# ProPrj_2025_7__2025-07-14.net
KiCad netlist of a schematic drawn in EasyEDA Pro
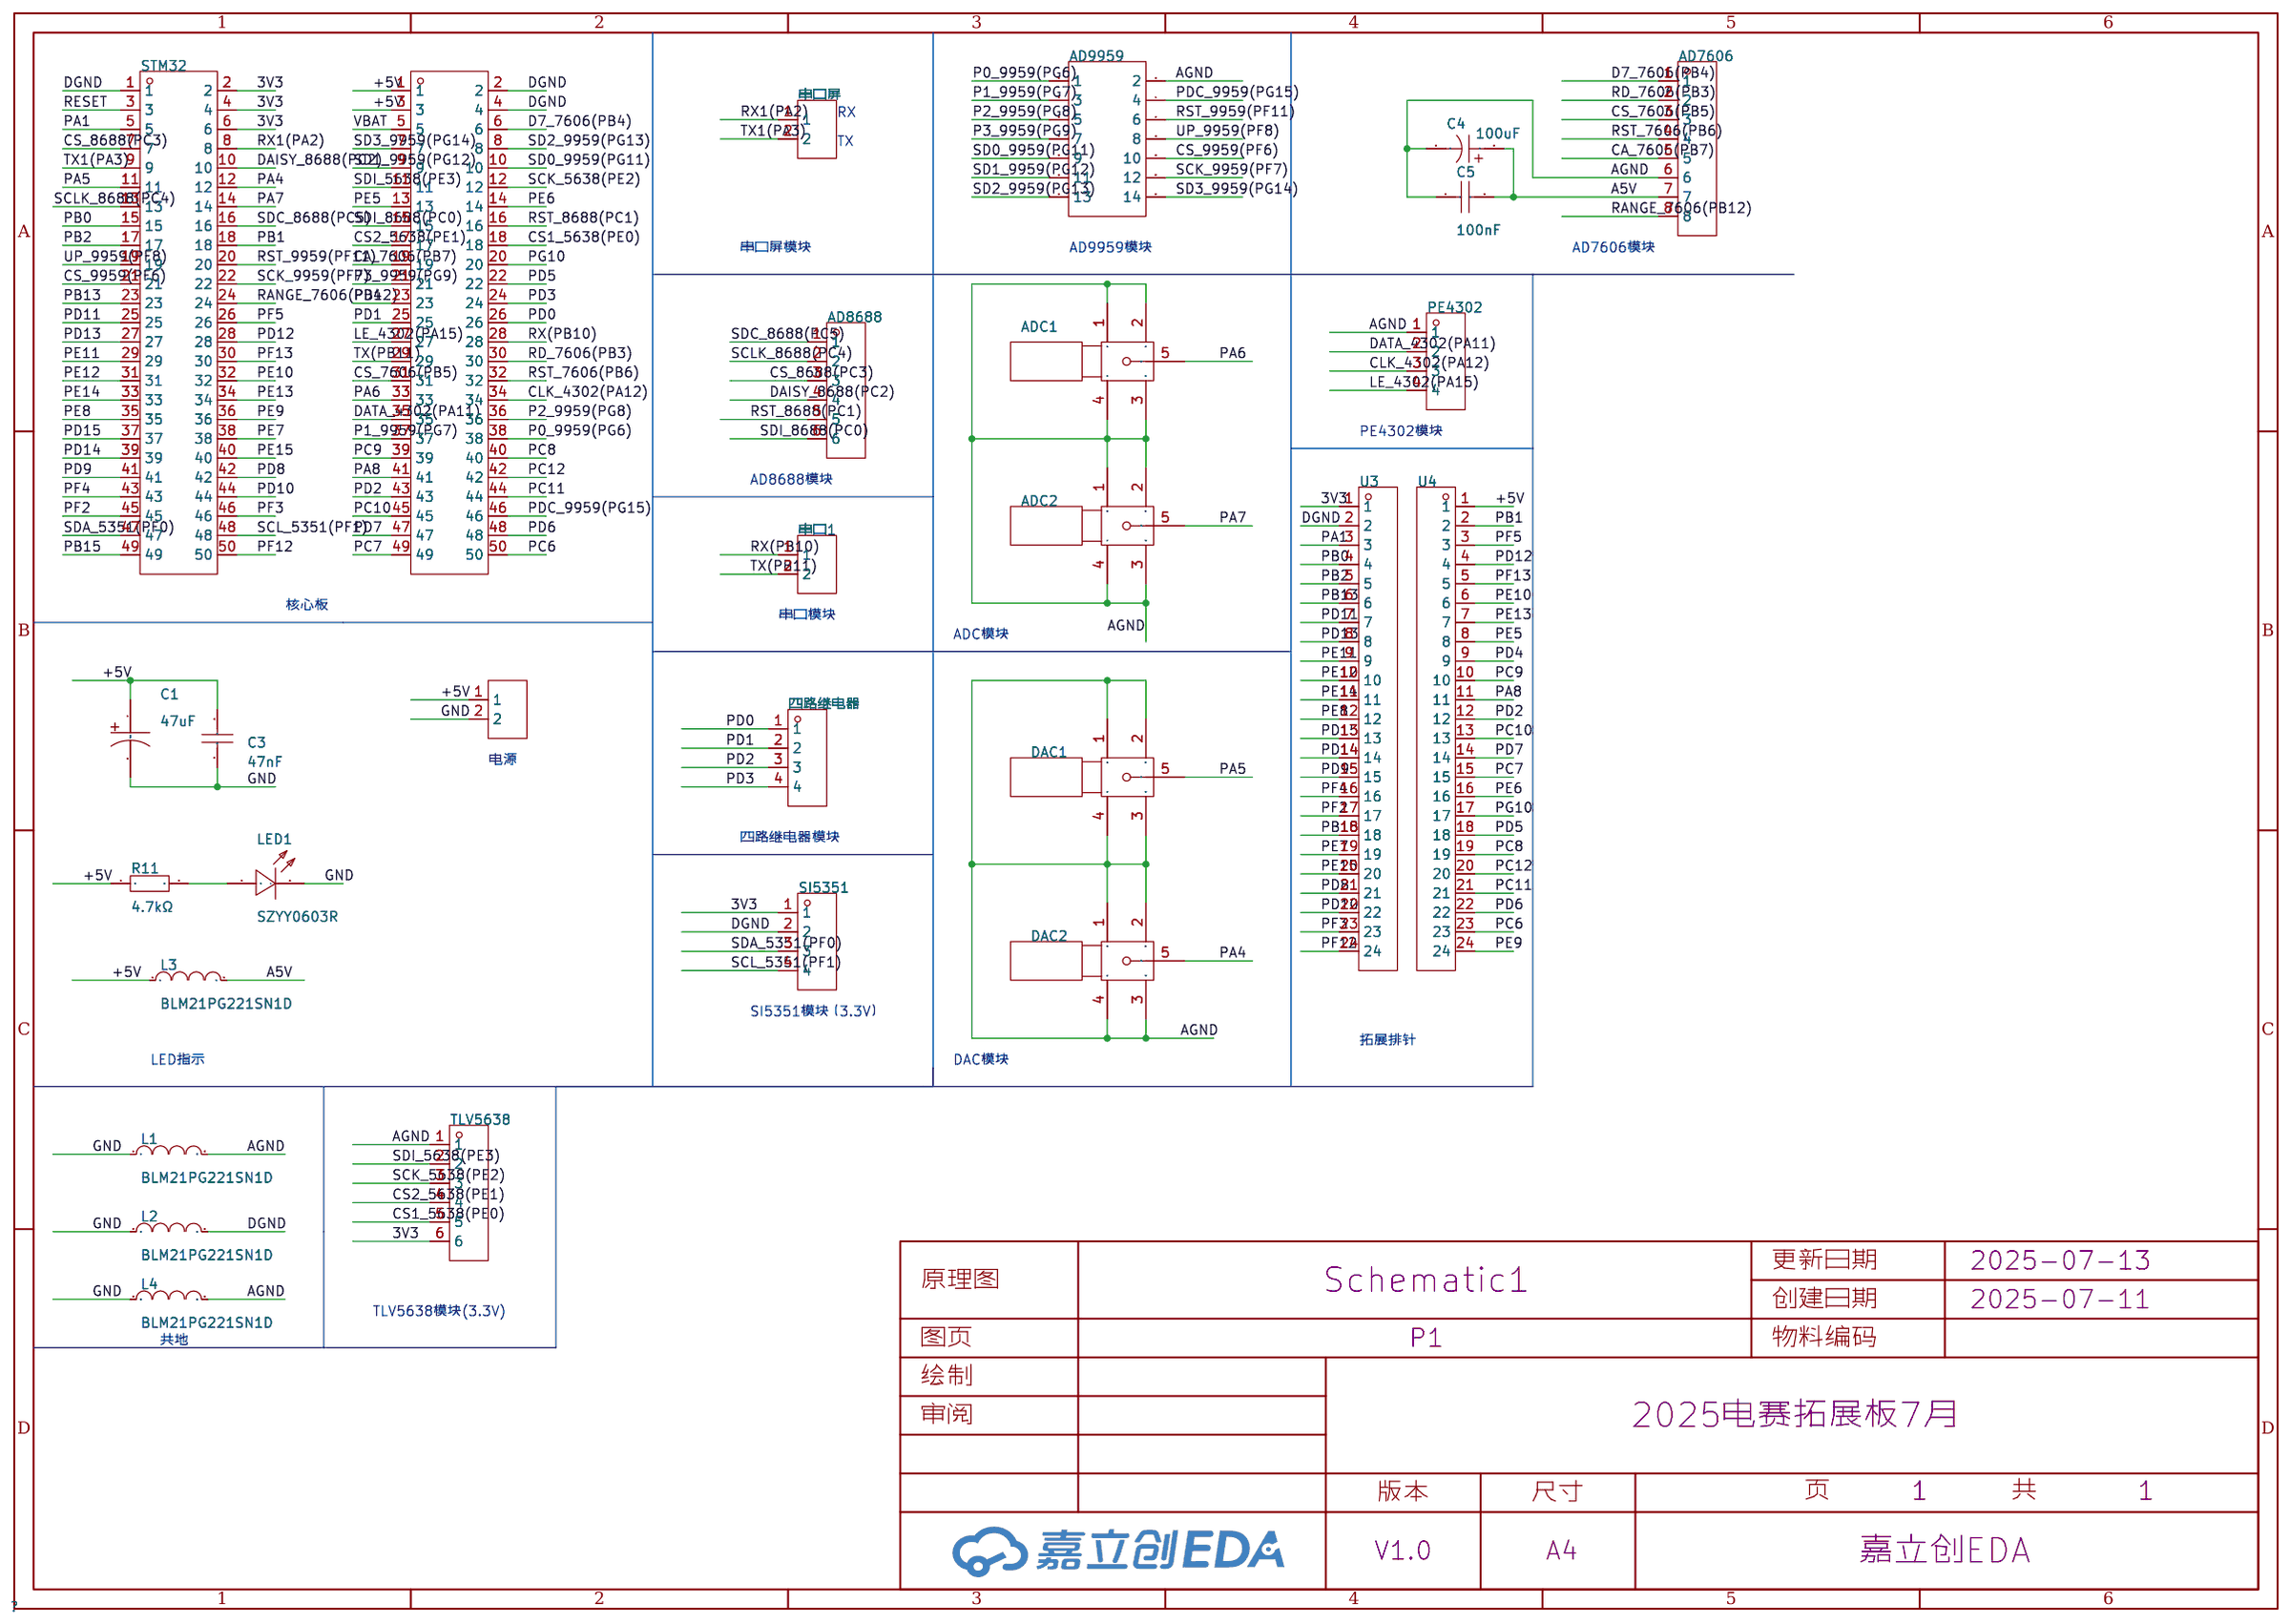
[diagram p0: schematic sheet]

(export (version "E")
  (design (tool "Eeschema 10.0.6"))
  (components
    (comp (ref "AD7606")
      (value "ZX-XH2.54-8PZZ")
      (footprint "easyedapro:CONN-TH_8P-P2.50-XH2.54-8P")
      (fields (field (name "Manufacturer") "Megastar(兆星)"))
      (libsource (lib "easyedapro") (part "ZX-XH2.54-8PZZ"))
    )
    (comp (ref "AD8688")
      (value "ZX-XH2.54-6PZZ")
      (footprint "easyedapro:CONN-TH_6P-P2.50_ZX-XH2.54-6PZZ")
      (fields (field (name "Manufacturer") "Megastar(兆星)"))
      (libsource (lib "easyedapro") (part "ZX-XH2.54-6PZZ"))
    )
    (comp (ref "AD9959")
      (value "2.54-2*7P简牛")
      (footprint "easyedapro:IDC-TH_14P-P2.54-V-R2-C7-S2.54")
      (description "连接器类型:简牛座;间距:2.54mm;结构:2x7P;封装形式:直插;行距:2.54mm;排数:2;每排PIN数:7;触头材质:黄铜;触头镀层:金;")
      (fields (field (name "Manufacturer") "BOOMELE(博穆精密)"))
      (libsource (lib "easyedapro") (part "HDR-IDC-2.54-2X7P"))
    )
    (comp (ref "ADC1")
      (value "BWSMA-KE-P001")
      (footprint "easyedapro:SMA-SMD_BWSMA-KE-P001")
      (description "连接器类型:板端;接口类型:内孔;端口数量:1;接口直径:5.2mm;接口长度/高度:-;频率-最大值:-;射频系列:SMA;阻抗:50Ω;样式:偏脚;工作温度范围:-;")
      (fields (field (name "Manufacturer") "BAT WIRELESS(蝙蝠无线)"))
      (libsource (lib "easyedapro") (part "BWSMA-KE-P001"))
    )
    (comp (ref "ADC2")
      (value "BWSMA-KE-P001")
      (footprint "easyedapro:SMA-SMD_BWSMA-KE-P001")
      (description "连接器类型:板端;接口类型:内孔;端口数量:1;接口直径:5.2mm;接口长度/高度:-;频率-最大值:-;射频系列:SMA;阻抗:50Ω;样式:偏脚;工作温度范围:-;")
      (fields (field (name "Manufacturer") "BAT WIRELESS(蝙蝠无线)"))
      (libsource (lib "easyedapro") (part "BWSMA-KE-P001"))
    )
    (comp (ref "C1")
      (value "47uF")
      (footprint "easyedapro:CAP-TH_BD5.0-P2.00-D0.8-FD")
      (description "容值:47uF;精度:±20%;额定电压:25V;纹波电流:250mA@100kHz;等效串联电阻(ESR):300mΩ@100kHz;")
      (fields
        (field (name "Manufacturer Part") "NXB25V47M5*11 2.5TP")
        (field (name "Manufacturer") "SAMYOUNG(韩国三莹)")
      )
      (libsource (lib "easyedapro") (part "NXB25VB47M5*11_2.5TP"))
    )
    (comp (ref "C3")
      (value "47nF")
      (footprint "easyedapro:C0805")
      (description "容值:47nF;精度:±10%;额定电压:50V;材质(温度系数):X7R;")
      (fields
        (field (name "Manufacturer Part") "CL21B473KBCNNNC")
        (field (name "Manufacturer") "SAMSUNG(三星)")
      )
      (libsource (lib "easyedapro") (part "CL21B473KBCNNNC"))
    )
    (comp (ref "C4")
      (value "100uF")
      (footprint "easyedapro:CAP-TH_BD8.0-P3.50-D0.5-FD")
      (description "容值:100uF;精度:±20%;额定电压:50V;纹波电流:680mA@120Hz;等效串联电阻(ESR):120mΩ;")
      (fields (field (name "Manufacturer Part") "ERG50V100M8X12") (field (name "Manufacturer") "捷而瑞"))
      (libsource (lib "easyedapro") (part "ERG50V100M8X12"))
    )
    (comp (ref "C5")
      (value "100nF")
      (footprint "easyedapro:C0805")
      (description "容值:100nF;精度:±10%;额定电压:50V;材质(温度系数):X7R;")
      (fields
        (field (name "Manufacturer Part") "CL21B104KBCNNNC")
        (field (name "Manufacturer") "SAMSUNG(三星)")
      )
      (libsource (lib "easyedapro") (part "CL21B104KBCNNNC"))
    )
    (comp (ref "DAC1")
      (value "BWSMA-KE-P001")
      (footprint "easyedapro:SMA-SMD_BWSMA-KE-P001")
      (description "连接器类型:板端;接口类型:内孔;端口数量:1;接口直径:5.2mm;接口长度/高度:-;频率-最大值:-;射频系列:SMA;阻抗:50Ω;样式:偏脚;工作温度范围:-;")
      (fields (field (name "Manufacturer") "BAT WIRELESS(蝙蝠无线)"))
      (libsource (lib "easyedapro") (part "BWSMA-KE-P001"))
    )
    (comp (ref "DAC2")
      (value "BWSMA-KE-P001")
      (footprint "easyedapro:SMA-SMD_BWSMA-KE-P001")
      (description "连接器类型:板端;接口类型:内孔;端口数量:1;接口直径:5.2mm;接口长度/高度:-;频率-最大值:-;射频系列:SMA;阻抗:50Ω;样式:偏脚;工作温度范围:-;")
      (fields (field (name "Manufacturer") "BAT WIRELESS(蝙蝠无线)"))
      (libsource (lib "easyedapro") (part "BWSMA-KE-P001"))
    )
    (comp (ref "L1")
      (value "BLM21PG221SN1D")
      (footprint "easyedapro:L0805")
      (description "标称阻抗@测试频率:220Ω@100MHz;误差:±25%;直流电阻(RDC):45mΩ;")
      (fields (field (name "Manufacturer") "muRata(村田)"))
      (libsource (lib "easyedapro") (part "BLM21PG221SN1D"))
    )
    (comp (ref "L2")
      (value "BLM21PG221SN1D")
      (footprint "easyedapro:L0805")
      (description "标称阻抗@测试频率:220Ω@100MHz;误差:±25%;直流电阻(RDC):45mΩ;")
      (fields (field (name "Manufacturer") "muRata(村田)"))
      (libsource (lib "easyedapro") (part "BLM21PG221SN1D"))
    )
    (comp (ref "L3")
      (value "BLM21PG221SN1D")
      (footprint "easyedapro:L0805")
      (description "标称阻抗@测试频率:220Ω@100MHz;误差:±25%;直流电阻(RDC):45mΩ;")
      (fields (field (name "Manufacturer") "muRata(村田)"))
      (libsource (lib "easyedapro") (part "BLM21PG221SN1D"))
    )
    (comp (ref "L4")
      (value "BLM21PG221SN1D")
      (footprint "easyedapro:L0805")
      (description "标称阻抗@测试频率:220Ω@100MHz;误差:±25%;直流电阻(RDC):45mΩ;")
      (fields (field (name "Manufacturer") "muRata(村田)"))
      (libsource (lib "easyedapro") (part "BLM21PG221SN1D"))
    )
    (comp (ref "LED1")
      (value "SZYY0603R")
      (footprint "easyedapro:LED0603-R-RD")
      (fields (field (name "Manufacturer") "yongyu(永裕光电)"))
      (libsource (lib "easyedapro") (part "SZYY0603R"))
    )
    (comp (ref "PE4302")
      (value "ZX-XH2.54-4PZZ")
      (footprint "easyedapro:CONN-TH_4P-P2.50_4PIN")
      (fields (field (name "Manufacturer") "Megastar(兆星)"))
      (libsource (lib "easyedapro") (part "ZX-XH2.54-4PZZ"))
    )
    (comp (ref "R11")
      (value "4.7kΩ")
      (footprint "easyedapro:R0805")
      (description "电阻类型:厚膜电阻;阻值:4.7kΩ;精度:±1%;功率:125mW;最大工作电压:150V;温度系数:±100ppm/°C;")
      (fields
        (field (name "Manufacturer Part") "0805W8F4701T5E")
        (field (name "Manufacturer") "UNI-ROYAL(厚声)")
      )
      (libsource (lib "easyedapro") (part "0805W8F4701T5E"))
    )
    (comp (ref "SI5351")
      (value "ZX-XH2.54-4PZZ")
      (footprint "easyedapro:CONN-TH_4P-P2.50_4PIN")
      (fields (field (name "Manufacturer") "Megastar(兆星)"))
      (libsource (lib "easyedapro") (part "ZX-XH2.54-4PZZ"))
    )
    (comp (ref "STM32")
      (value "ZX-PM2.54-2-25PY")
      (footprint "easyedapro:HDR-TH_50P-P2.54-V-F-R2-C25-S2.54-1")
      (fields (field (name "Manufacturer") "Megastar(兆星)"))
      (libsource (lib "easyedapro") (part "ZX-PM2.54-2-25PY"))
    )
    (comp (ref "TLV5638")
      (value "ZX-XH2.54-6PZZ")
      (footprint "easyedapro:CONN-TH_6P-P2.50_ZX-XH2.54-6PZZ")
      (fields (field (name "Manufacturer") "Megastar(兆星)"))
      (libsource (lib "easyedapro") (part "ZX-XH2.54-6PZZ"))
    )
    (comp (ref "U2")
      (value "ZX-PM2.54-2-25PY")
      (footprint "easyedapro:HDR-TH_50P-P2.54-V-F-R2-C25-S2.54-1")
      (fields (field (name "Manufacturer") "Megastar(兆星)"))
      (libsource (lib "easyedapro") (part "ZX-PM2.54-2-25PY"))
    )
    (comp (ref "U3")
      (value "HC-PM254-8.5H-1x24PZ")
      (footprint "easyedapro:HDR-TH_24P-P2.54-V-F")
      (fields (field (name "Manufacturer") "HC(虹成电子)"))
      (libsource (lib "easyedapro") (part "HC-PM254-8.5H-1X24PZ"))
    )
    (comp (ref "U4")
      (value "HC-PM254-8.5H-1x24PZ")
      (footprint "easyedapro:HDR-TH_24P-P2.54-V-F")
      (fields (field (name "Manufacturer") "HC(虹成电子)"))
      (libsource (lib "easyedapro") (part "HC-PM254-8.5H-1X24PZ"))
    )
    (comp (ref "串口")
      (value "ZX-XH2.54-2PZZ")
      (footprint "easyedapro:CONN-TH_2P-P2.50_HX25003-2A")
      (fields (field (name "Manufacturer") "Megastar(兆星)"))
      (libsource (lib "easyedapro") (part "ZX-XH2.54-2PZZ"))
    )
    (comp (ref "串口1")
      (value "ZX-XH2.54-2PZZ")
      (footprint "easyedapro:CONN-TH_2P-P2.50_HX25003-2A")
      (fields (field (name "Manufacturer") "Megastar(兆星)"))
      (libsource (lib "easyedapro") (part "ZX-XH2.54-2PZZ"))
    )
    (comp (ref "串口屏")
      (value "ZX-XH2.54-2PZZ")
      (footprint "easyedapro:CONN-TH_2P-P2.50_HX25003-2A")
      (fields (field (name "Manufacturer") "Megastar(兆星)"))
      (libsource (lib "easyedapro") (part "ZX-XH2.54-2PZZ"))
    )
    (comp (ref "四路继电器")
      (value "ZX-XH2.54-4PZZ")
      (footprint "easyedapro:CONN-TH_4P-P2.50_4PIN")
      (fields (field (name "Manufacturer") "Megastar(兆星)"))
      (libsource (lib "easyedapro") (part "ZX-XH2.54-4PZZ"))
    )
  )
  (nets
    (net (code "1") (name "/+5V") (class "Default")
      (node (ref "C1") (pin "1") (pinfunction "1_1") (pintype "unspecified"))
      (node (ref "C3") (pin "2") (pinfunction "2_2") (pintype "input"))
      (node (ref "L3") (pin "1") (pinfunction "1_1") (pintype "unspecified"))
      (node (ref "R11") (pin "1") (pinfunction "1_1") (pintype "input"))
      (node (ref "U2") (pin "1") (pinfunction "1_1") (pintype "unspecified"))
      (node (ref "U2") (pin "3") (pinfunction "3_3") (pintype "unspecified"))
      (node (ref "U4") (pin "1") (pinfunction "1_1") (pintype "unspecified"))
      (node (ref "串口") (pin "1") (pinfunction "1_1") (pintype "unspecified"))
    )
    (net (code "2") (name "/3V3") (class "Default")
      (node (ref "SI5351") (pin "1") (pinfunction "1_1") (pintype "unspecified"))
      (node (ref "STM32") (pin "2") (pinfunction "2_2") (pintype "unspecified"))
      (node (ref "STM32") (pin "4") (pinfunction "4_4") (pintype "unspecified"))
      (node (ref "STM32") (pin "6") (pinfunction "6_6") (pintype "unspecified"))
      (node (ref "TLV5638") (pin "6") (pinfunction "6_6") (pintype "unspecified"))
      (node (ref "U3") (pin "1") (pinfunction "1_1") (pintype "unspecified"))
    )
    (net (code "3") (name "/A5V") (class "Default")
      (node (ref "AD7606") (pin "7") (pinfunction "7_7") (pintype "unspecified"))
      (node (ref "C4") (pin "1") (pinfunction "1_1") (pintype "input"))
      (node (ref "C5") (pin "2") (pinfunction "2_2") (pintype "input"))
      (node (ref "L3") (pin "2") (pinfunction "2_2") (pintype "unspecified"))
    )
    (net (code "4") (name "/AGND") (class "Default")
      (node (ref "AD7606") (pin "6") (pinfunction "6_6") (pintype "unspecified"))
      (node (ref "AD9959") (pin "2") (pinfunction "2_2") (pintype "unspecified"))
      (node (ref "ADC1") (pin "1") (pinfunction "1_1") (pintype "unspecified"))
      (node (ref "ADC1") (pin "2") (pinfunction "2_2") (pintype "unspecified"))
      (node (ref "ADC1") (pin "3") (pinfunction "3_3") (pintype "unspecified"))
      (node (ref "ADC1") (pin "4") (pinfunction "4_4") (pintype "unspecified"))
      (node (ref "ADC2") (pin "1") (pinfunction "1_1") (pintype "unspecified"))
      (node (ref "ADC2") (pin "2") (pinfunction "2_2") (pintype "unspecified"))
      (node (ref "ADC2") (pin "3") (pinfunction "3_3") (pintype "unspecified"))
      (node (ref "ADC2") (pin "4") (pinfunction "4_4") (pintype "unspecified"))
      (node (ref "C4") (pin "2") (pinfunction "2_2") (pintype "input"))
      (node (ref "C5") (pin "1") (pinfunction "1_1") (pintype "input"))
      (node (ref "DAC1") (pin "1") (pinfunction "1_1") (pintype "unspecified"))
      (node (ref "DAC1") (pin "2") (pinfunction "2_2") (pintype "unspecified"))
      (node (ref "DAC1") (pin "3") (pinfunction "3_3") (pintype "unspecified"))
      (node (ref "DAC1") (pin "4") (pinfunction "4_4") (pintype "unspecified"))
      (node (ref "DAC2") (pin "1") (pinfunction "1_1") (pintype "unspecified"))
      (node (ref "DAC2") (pin "2") (pinfunction "2_2") (pintype "unspecified"))
      (node (ref "DAC2") (pin "3") (pinfunction "3_3") (pintype "unspecified"))
      (node (ref "DAC2") (pin "4") (pinfunction "4_4") (pintype "unspecified"))
      (node (ref "L1") (pin "2") (pinfunction "2_2") (pintype "unspecified"))
      (node (ref "L4") (pin "2") (pinfunction "2_2") (pintype "unspecified"))
      (node (ref "PE4302") (pin "1") (pinfunction "1_1") (pintype "unspecified"))
      (node (ref "TLV5638") (pin "1") (pinfunction "1_1") (pintype "unspecified"))
    )
    (net (code "5") (name "/CA_7606(PB7)") (class "Default")
      (node (ref "AD7606") (pin "5") (pinfunction "5_5") (pintype "unspecified"))
      (node (ref "U2") (pin "19") (pinfunction "19_19") (pintype "unspecified"))
    )
    (net (code "6") (name "/CLK_4302(PA12)") (class "Default")
      (node (ref "PE4302") (pin "3") (pinfunction "3_3") (pintype "unspecified"))
      (node (ref "U2") (pin "34") (pinfunction "34_34") (pintype "unspecified"))
    )
    (net (code "7") (name "/CS1_5638(PE0)") (class "Default")
      (node (ref "TLV5638") (pin "5") (pinfunction "5_5") (pintype "unspecified"))
      (node (ref "U2") (pin "18") (pinfunction "18_18") (pintype "unspecified"))
    )
    (net (code "8") (name "/CS2_5638(PE1)") (class "Default")
      (node (ref "TLV5638") (pin "4") (pinfunction "4_4") (pintype "unspecified"))
      (node (ref "U2") (pin "17") (pinfunction "17_17") (pintype "unspecified"))
    )
    (net (code "9") (name "/CS_7606(PB5)") (class "Default")
      (node (ref "AD7606") (pin "3") (pinfunction "3_3") (pintype "unspecified"))
      (node (ref "U2") (pin "31") (pinfunction "31_31") (pintype "unspecified"))
    )
    (net (code "10") (name "/CS_8688(PC3)") (class "Default")
      (node (ref "AD8688") (pin "3") (pinfunction "3_3") (pintype "unspecified"))
      (node (ref "STM32") (pin "7") (pinfunction "7_7") (pintype "unspecified"))
    )
    (net (code "11") (name "/CS_9959(PF6)") (class "Default")
      (node (ref "AD9959") (pin "10") (pinfunction "10_10") (pintype "unspecified"))
      (node (ref "STM32") (pin "21") (pinfunction "21_21") (pintype "unspecified"))
    )
    (net (code "12") (name "/D7_7606(PB4)") (class "Default")
      (node (ref "AD7606") (pin "1") (pinfunction "1_1") (pintype "unspecified"))
      (node (ref "U2") (pin "6") (pinfunction "6_6") (pintype "unspecified"))
    )
    (net (code "13") (name "/DAISY_8688(PC2)") (class "Default")
      (node (ref "AD8688") (pin "4") (pinfunction "4_4") (pintype "unspecified"))
      (node (ref "STM32") (pin "10") (pinfunction "10_10") (pintype "unspecified"))
    )
    (net (code "14") (name "/DATA_4302(PA11)") (class "Default")
      (node (ref "PE4302") (pin "2") (pinfunction "2_2") (pintype "unspecified"))
      (node (ref "U2") (pin "35") (pinfunction "35_35") (pintype "unspecified"))
    )
    (net (code "15") (name "/DGND") (class "Default")
      (node (ref "L2") (pin "2") (pinfunction "2_2") (pintype "unspecified"))
      (node (ref "SI5351") (pin "2") (pinfunction "2_2") (pintype "unspecified"))
      (node (ref "STM32") (pin "1") (pinfunction "1_1") (pintype "unspecified"))
      (node (ref "U2") (pin "2") (pinfunction "2_2") (pintype "unspecified"))
      (node (ref "U2") (pin "4") (pinfunction "4_4") (pintype "unspecified"))
      (node (ref "U3") (pin "2") (pinfunction "2_2") (pintype "unspecified"))
    )
    (net (code "16") (name "/GND") (class "Default")
      (node (ref "C1") (pin "2") (pinfunction "2_2") (pintype "unspecified"))
      (node (ref "C3") (pin "1") (pinfunction "1_1") (pintype "input"))
      (node (ref "L1") (pin "1") (pinfunction "1_1") (pintype "unspecified"))
      (node (ref "L2") (pin "1") (pinfunction "1_1") (pintype "unspecified"))
      (node (ref "L4") (pin "1") (pinfunction "1_1") (pintype "unspecified"))
      (node (ref "LED1") (pin "2") (pinfunction "-_2") (pintype "unspecified"))
      (node (ref "串口") (pin "2") (pinfunction "2_2") (pintype "unspecified"))
    )
    (net (code "17") (name "/LE_4302(PA15)") (class "Default")
      (node (ref "PE4302") (pin "4") (pinfunction "4_4") (pintype "unspecified"))
      (node (ref "U2") (pin "27") (pinfunction "27_27") (pintype "unspecified"))
    )
    (net (code "18") (name "/P0_9959(PG6)") (class "Default")
      (node (ref "AD9959") (pin "1") (pinfunction "1_1") (pintype "unspecified"))
      (node (ref "U2") (pin "38") (pinfunction "38_38") (pintype "unspecified"))
    )
    (net (code "19") (name "/P1_9959(PG7)") (class "Default")
      (node (ref "AD9959") (pin "3") (pinfunction "3_3") (pintype "unspecified"))
      (node (ref "U2") (pin "37") (pinfunction "37_37") (pintype "unspecified"))
    )
    (net (code "20") (name "/P2_9959(PG8)") (class "Default")
      (node (ref "AD9959") (pin "5") (pinfunction "5_5") (pintype "unspecified"))
      (node (ref "U2") (pin "36") (pinfunction "36_36") (pintype "unspecified"))
    )
    (net (code "21") (name "/P3_9959(PG9)") (class "Default")
      (node (ref "AD9959") (pin "7") (pinfunction "7_7") (pintype "unspecified"))
      (node (ref "U2") (pin "21") (pinfunction "21_21") (pintype "unspecified"))
    )
    (net (code "22") (name "/PA1") (class "Default")
      (node (ref "STM32") (pin "5") (pinfunction "5_5") (pintype "unspecified"))
      (node (ref "U3") (pin "3") (pinfunction "3_3") (pintype "unspecified"))
    )
    (net (code "23") (name "/PA4") (class "Default")
      (node (ref "DAC2") (pin "5") (pinfunction "5_5") (pintype "unspecified"))
      (node (ref "STM32") (pin "12") (pinfunction "12_12") (pintype "unspecified"))
    )
    (net (code "24") (name "/PA5") (class "Default")
      (node (ref "DAC1") (pin "5") (pinfunction "5_5") (pintype "unspecified"))
      (node (ref "STM32") (pin "11") (pinfunction "11_11") (pintype "unspecified"))
    )
    (net (code "25") (name "/PA6") (class "Default")
      (node (ref "ADC1") (pin "5") (pinfunction "5_5") (pintype "unspecified"))
      (node (ref "U2") (pin "33") (pinfunction "33_33") (pintype "unspecified"))
    )
    (net (code "26") (name "/PA7") (class "Default")
      (node (ref "ADC2") (pin "5") (pinfunction "5_5") (pintype "unspecified"))
      (node (ref "STM32") (pin "14") (pinfunction "14_14") (pintype "unspecified"))
    )
    (net (code "27") (name "/PA8") (class "Default")
      (node (ref "U2") (pin "41") (pinfunction "41_41") (pintype "unspecified"))
      (node (ref "U4") (pin "11") (pinfunction "11_11") (pintype "unspecified"))
    )
    (net (code "28") (name "/PB0") (class "Default")
      (node (ref "STM32") (pin "15") (pinfunction "15_15") (pintype "unspecified"))
      (node (ref "U3") (pin "4") (pinfunction "4_4") (pintype "unspecified"))
    )
    (net (code "29") (name "/PB1") (class "Default")
      (node (ref "STM32") (pin "18") (pinfunction "18_18") (pintype "unspecified"))
      (node (ref "U4") (pin "2") (pinfunction "2_2") (pintype "unspecified"))
    )
    (net (code "30") (name "/PB2") (class "Default")
      (node (ref "STM32") (pin "17") (pinfunction "17_17") (pintype "unspecified"))
      (node (ref "U3") (pin "5") (pinfunction "5_5") (pintype "unspecified"))
    )
    (net (code "31") (name "/PB13") (class "Default")
      (node (ref "STM32") (pin "23") (pinfunction "23_23") (pintype "unspecified"))
      (node (ref "U3") (pin "6") (pinfunction "6_6") (pintype "unspecified"))
    )
    (net (code "32") (name "/PB15") (class "Default")
      (node (ref "STM32") (pin "49") (pinfunction "49_49") (pintype "unspecified"))
      (node (ref "U3") (pin "18") (pinfunction "18_18") (pintype "unspecified"))
    )
    (net (code "33") (name "/PC6") (class "Default")
      (node (ref "U2") (pin "50") (pinfunction "50_50") (pintype "unspecified"))
      (node (ref "U4") (pin "23") (pinfunction "23_23") (pintype "unspecified"))
    )
    (net (code "34") (name "/PC7") (class "Default")
      (node (ref "U2") (pin "49") (pinfunction "49_49") (pintype "unspecified"))
      (node (ref "U4") (pin "15") (pinfunction "15_15") (pintype "unspecified"))
    )
    (net (code "35") (name "/PC8") (class "Default")
      (node (ref "U2") (pin "40") (pinfunction "40_40") (pintype "unspecified"))
      (node (ref "U4") (pin "19") (pinfunction "19_19") (pintype "unspecified"))
    )
    (net (code "36") (name "/PC9") (class "Default")
      (node (ref "U2") (pin "39") (pinfunction "39_39") (pintype "unspecified"))
      (node (ref "U4") (pin "10") (pinfunction "10_10") (pintype "unspecified"))
    )
    (net (code "37") (name "/PC10") (class "Default")
      (node (ref "U2") (pin "45") (pinfunction "45_45") (pintype "unspecified"))
      (node (ref "U4") (pin "13") (pinfunction "13_13") (pintype "unspecified"))
    )
    (net (code "38") (name "/PC11") (class "Default")
      (node (ref "U2") (pin "44") (pinfunction "44_44") (pintype "unspecified"))
      (node (ref "U4") (pin "21") (pinfunction "21_21") (pintype "unspecified"))
    )
    (net (code "39") (name "/PC12") (class "Default")
      (node (ref "U2") (pin "42") (pinfunction "42_42") (pintype "unspecified"))
      (node (ref "U4") (pin "20") (pinfunction "20_20") (pintype "unspecified"))
    )
    (net (code "40") (name "/PD0") (class "Default")
      (node (ref "U2") (pin "26") (pinfunction "26_26") (pintype "unspecified"))
      (node (ref "四路继电器") (pin "1") (pinfunction "1_1") (pintype "unspecified"))
    )
    (net (code "41") (name "/PD1") (class "Default")
      (node (ref "U2") (pin "25") (pinfunction "25_25") (pintype "unspecified"))
      (node (ref "四路继电器") (pin "2") (pinfunction "2_2") (pintype "unspecified"))
    )
    (net (code "42") (name "/PD2") (class "Default")
      (node (ref "U2") (pin "43") (pinfunction "43_43") (pintype "unspecified"))
      (node (ref "U4") (pin "12") (pinfunction "12_12") (pintype "unspecified"))
      (node (ref "四路继电器") (pin "3") (pinfunction "3_3") (pintype "unspecified"))
    )
    (net (code "43") (name "/PD3") (class "Default")
      (node (ref "U2") (pin "24") (pinfunction "24_24") (pintype "unspecified"))
      (node (ref "四路继电器") (pin "4") (pinfunction "4_4") (pintype "unspecified"))
    )
    (net (code "44") (name "/PD4") (class "Default")
      (node (ref "U2") (pin "23") (pinfunction "23_23") (pintype "unspecified"))
      (node (ref "U4") (pin "9") (pinfunction "9_9") (pintype "unspecified"))
    )
    (net (code "45") (name "/PD5") (class "Default")
      (node (ref "U2") (pin "22") (pinfunction "22_22") (pintype "unspecified"))
      (node (ref "U4") (pin "18") (pinfunction "18_18") (pintype "unspecified"))
    )
    (net (code "46") (name "/PD6") (class "Default")
      (node (ref "U2") (pin "48") (pinfunction "48_48") (pintype "unspecified"))
      (node (ref "U4") (pin "22") (pinfunction "22_22") (pintype "unspecified"))
    )
    (net (code "47") (name "/PD7") (class "Default")
      (node (ref "U2") (pin "47") (pinfunction "47_47") (pintype "unspecified"))
      (node (ref "U4") (pin "14") (pinfunction "14_14") (pintype "unspecified"))
    )
    (net (code "48") (name "/PD8") (class "Default")
      (node (ref "STM32") (pin "42") (pinfunction "42_42") (pintype "unspecified"))
      (node (ref "U3") (pin "21") (pinfunction "21_21") (pintype "unspecified"))
    )
    (net (code "49") (name "/PD9") (class "Default")
      (node (ref "STM32") (pin "41") (pinfunction "41_41") (pintype "unspecified"))
      (node (ref "U3") (pin "15") (pinfunction "15_15") (pintype "unspecified"))
    )
    (net (code "50") (name "/PD10") (class "Default")
      (node (ref "STM32") (pin "44") (pinfunction "44_44") (pintype "unspecified"))
      (node (ref "U3") (pin "22") (pinfunction "22_22") (pintype "unspecified"))
    )
    (net (code "51") (name "/PD11") (class "Default")
      (node (ref "STM32") (pin "25") (pinfunction "25_25") (pintype "unspecified"))
      (node (ref "U3") (pin "7") (pinfunction "7_7") (pintype "unspecified"))
    )
    (net (code "52") (name "/PD12") (class "Default")
      (node (ref "STM32") (pin "28") (pinfunction "28_28") (pintype "unspecified"))
      (node (ref "U4") (pin "4") (pinfunction "4_4") (pintype "unspecified"))
    )
    (net (code "53") (name "/PD13") (class "Default")
      (node (ref "STM32") (pin "27") (pinfunction "27_27") (pintype "unspecified"))
      (node (ref "U3") (pin "8") (pinfunction "8_8") (pintype "unspecified"))
    )
    (net (code "54") (name "/PD14") (class "Default")
      (node (ref "STM32") (pin "39") (pinfunction "39_39") (pintype "unspecified"))
      (node (ref "U3") (pin "14") (pinfunction "14_14") (pintype "unspecified"))
    )
    (net (code "55") (name "/PD15") (class "Default")
      (node (ref "STM32") (pin "37") (pinfunction "37_37") (pintype "unspecified"))
      (node (ref "U3") (pin "13") (pinfunction "13_13") (pintype "unspecified"))
    )
    (net (code "56") (name "/PDC_9959(PG15)") (class "Default")
      (node (ref "AD9959") (pin "4") (pinfunction "4_4") (pintype "unspecified"))
      (node (ref "U2") (pin "46") (pinfunction "46_46") (pintype "unspecified"))
    )
    (net (code "57") (name "/PE5") (class "Default")
      (node (ref "U2") (pin "13") (pinfunction "13_13") (pintype "unspecified"))
      (node (ref "U4") (pin "8") (pinfunction "8_8") (pintype "unspecified"))
    )
    (net (code "58") (name "/PE6") (class "Default")
      (node (ref "U2") (pin "14") (pinfunction "14_14") (pintype "unspecified"))
      (node (ref "U4") (pin "16") (pinfunction "16_16") (pintype "unspecified"))
    )
    (net (code "59") (name "/PE7") (class "Default")
      (node (ref "STM32") (pin "38") (pinfunction "38_38") (pintype "unspecified"))
      (node (ref "U3") (pin "19") (pinfunction "19_19") (pintype "unspecified"))
    )
    (net (code "60") (name "/PE8") (class "Default")
      (node (ref "STM32") (pin "35") (pinfunction "35_35") (pintype "unspecified"))
      (node (ref "U3") (pin "12") (pinfunction "12_12") (pintype "unspecified"))
    )
    (net (code "61") (name "/PE9") (class "Default")
      (node (ref "STM32") (pin "36") (pinfunction "36_36") (pintype "unspecified"))
      (node (ref "U4") (pin "24") (pinfunction "24_24") (pintype "unspecified"))
    )
    (net (code "62") (name "/PE10") (class "Default")
      (node (ref "STM32") (pin "32") (pinfunction "32_32") (pintype "unspecified"))
      (node (ref "U4") (pin "6") (pinfunction "6_6") (pintype "unspecified"))
    )
    (net (code "63") (name "/PE11") (class "Default")
      (node (ref "STM32") (pin "29") (pinfunction "29_29") (pintype "unspecified"))
      (node (ref "U3") (pin "9") (pinfunction "9_9") (pintype "unspecified"))
    )
    (net (code "64") (name "/PE12") (class "Default")
      (node (ref "STM32") (pin "31") (pinfunction "31_31") (pintype "unspecified"))
      (node (ref "U3") (pin "10") (pinfunction "10_10") (pintype "unspecified"))
    )
    (net (code "65") (name "/PE13") (class "Default")
      (node (ref "STM32") (pin "34") (pinfunction "34_34") (pintype "unspecified"))
      (node (ref "U4") (pin "7") (pinfunction "7_7") (pintype "unspecified"))
    )
    (net (code "66") (name "/PE14") (class "Default")
      (node (ref "STM32") (pin "33") (pinfunction "33_33") (pintype "unspecified"))
      (node (ref "U3") (pin "11") (pinfunction "11_11") (pintype "unspecified"))
    )
    (net (code "67") (name "/PE15") (class "Default")
      (node (ref "STM32") (pin "40") (pinfunction "40_40") (pintype "unspecified"))
      (node (ref "U3") (pin "20") (pinfunction "20_20") (pintype "unspecified"))
    )
    (net (code "68") (name "/PF2") (class "Default")
      (node (ref "STM32") (pin "45") (pinfunction "45_45") (pintype "unspecified"))
      (node (ref "U3") (pin "17") (pinfunction "17_17") (pintype "unspecified"))
    )
    (net (code "69") (name "/PF3") (class "Default")
      (node (ref "STM32") (pin "46") (pinfunction "46_46") (pintype "unspecified"))
      (node (ref "U3") (pin "23") (pinfunction "23_23") (pintype "unspecified"))
    )
    (net (code "70") (name "/PF4") (class "Default")
      (node (ref "STM32") (pin "43") (pinfunction "43_43") (pintype "unspecified"))
      (node (ref "U3") (pin "16") (pinfunction "16_16") (pintype "unspecified"))
    )
    (net (code "71") (name "/PF5") (class "Default")
      (node (ref "STM32") (pin "26") (pinfunction "26_26") (pintype "unspecified"))
      (node (ref "U4") (pin "3") (pinfunction "3_3") (pintype "unspecified"))
    )
    (net (code "72") (name "/PF12") (class "Default")
      (node (ref "STM32") (pin "50") (pinfunction "50_50") (pintype "unspecified"))
      (node (ref "U3") (pin "24") (pinfunction "24_24") (pintype "unspecified"))
    )
    (net (code "73") (name "/PF13") (class "Default")
      (node (ref "STM32") (pin "30") (pinfunction "30_30") (pintype "unspecified"))
      (node (ref "U4") (pin "5") (pinfunction "5_5") (pintype "unspecified"))
    )
    (net (code "74") (name "/PG10") (class "Default")
      (node (ref "U2") (pin "20") (pinfunction "20_20") (pintype "unspecified"))
      (node (ref "U4") (pin "17") (pinfunction "17_17") (pintype "unspecified"))
    )
    (net (code "75") (name "/RANGE_7606(PB12)") (class "Default")
      (node (ref "AD7606") (pin "8") (pinfunction "8_8") (pintype "unspecified"))
      (node (ref "STM32") (pin "24") (pinfunction "24_24") (pintype "unspecified"))
    )
    (net (code "76") (name "/RD_7606(PB3)") (class "Default")
      (node (ref "AD7606") (pin "2") (pinfunction "2_2") (pintype "unspecified"))
      (node (ref "U2") (pin "30") (pinfunction "30_30") (pintype "unspecified"))
    )
    (net (code "77") (name "/RESET") (class "Default")
      (node (ref "STM32") (pin "3") (pinfunction "3_3") (pintype "unspecified"))
    )
    (net (code "78") (name "/RST_7606(PB6)") (class "Default")
      (node (ref "AD7606") (pin "4") (pinfunction "4_4") (pintype "unspecified"))
      (node (ref "U2") (pin "32") (pinfunction "32_32") (pintype "unspecified"))
    )
    (net (code "79") (name "/RST_8688(PC1)") (class "Default")
      (node (ref "AD8688") (pin "5") (pinfunction "5_5") (pintype "unspecified"))
      (node (ref "U2") (pin "16") (pinfunction "16_16") (pintype "unspecified"))
    )
    (net (code "80") (name "/RST_9959(PF11)") (class "Default")
      (node (ref "AD9959") (pin "6") (pinfunction "6_6") (pintype "unspecified"))
      (node (ref "STM32") (pin "20") (pinfunction "20_20") (pintype "unspecified"))
    )
    (net (code "81") (name "/RX(PB10)") (class "Default")
      (node (ref "U2") (pin "28") (pinfunction "28_28") (pintype "unspecified"))
      (node (ref "串口1") (pin "1") (pinfunction "1_1") (pintype "unspecified"))
    )
    (net (code "82") (name "/RX1(PA2)") (class "Default")
      (node (ref "STM32") (pin "8") (pinfunction "8_8") (pintype "unspecified"))
      (node (ref "串口屏") (pin "1") (pinfunction "1_1") (pintype "unspecified"))
    )
    (net (code "83") (name "/SCK_5638(PE2)") (class "Default")
      (node (ref "TLV5638") (pin "3") (pinfunction "3_3") (pintype "unspecified"))
      (node (ref "U2") (pin "12") (pinfunction "12_12") (pintype "unspecified"))
    )
    (net (code "84") (name "/SCK_9959(PF7)") (class "Default")
      (node (ref "AD9959") (pin "12") (pinfunction "12_12") (pintype "unspecified"))
      (node (ref "STM32") (pin "22") (pinfunction "22_22") (pintype "unspecified"))
    )
    (net (code "85") (name "/SCLK_8688(PC4)") (class "Default")
      (node (ref "AD8688") (pin "2") (pinfunction "2_2") (pintype "unspecified"))
      (node (ref "STM32") (pin "13") (pinfunction "13_13") (pintype "unspecified"))
    )
    (net (code "86") (name "/SCL_5351(PF1)") (class "Default")
      (node (ref "SI5351") (pin "4") (pinfunction "4_4") (pintype "unspecified"))
      (node (ref "STM32") (pin "48") (pinfunction "48_48") (pintype "unspecified"))
    )
    (net (code "87") (name "/SD0_9959(PG11)") (class "Default")
      (node (ref "AD9959") (pin "9") (pinfunction "9_9") (pintype "unspecified"))
      (node (ref "U2") (pin "10") (pinfunction "10_10") (pintype "unspecified"))
    )
    (net (code "88") (name "/SD1_9959(PG12)") (class "Default")
      (node (ref "AD9959") (pin "11") (pinfunction "11_11") (pintype "unspecified"))
      (node (ref "U2") (pin "9") (pinfunction "9_9") (pintype "unspecified"))
    )
    (net (code "89") (name "/SD2_9959(PG13)") (class "Default")
      (node (ref "AD9959") (pin "13") (pinfunction "13_13") (pintype "unspecified"))
      (node (ref "U2") (pin "8") (pinfunction "8_8") (pintype "unspecified"))
    )
    (net (code "90") (name "/SD3_9959(PG14)") (class "Default")
      (node (ref "AD9959") (pin "14") (pinfunction "14_14") (pintype "unspecified"))
      (node (ref "U2") (pin "7") (pinfunction "7_7") (pintype "unspecified"))
    )
    (net (code "91") (name "/SDA_5351(PF0)") (class "Default")
      (node (ref "SI5351") (pin "3") (pinfunction "3_3") (pintype "unspecified"))
      (node (ref "STM32") (pin "47") (pinfunction "47_47") (pintype "unspecified"))
    )
    (net (code "92") (name "/SDC_8688(PC5)") (class "Default")
      (node (ref "AD8688") (pin "1") (pinfunction "1_1") (pintype "unspecified"))
      (node (ref "STM32") (pin "16") (pinfunction "16_16") (pintype "unspecified"))
    )
    (net (code "93") (name "/SDI_5638(PE3)") (class "Default")
      (node (ref "TLV5638") (pin "2") (pinfunction "2_2") (pintype "unspecified"))
      (node (ref "U2") (pin "11") (pinfunction "11_11") (pintype "unspecified"))
    )
    (net (code "94") (name "/SDI_8688(PC0)") (class "Default")
      (node (ref "AD8688") (pin "6") (pinfunction "6_6") (pintype "unspecified"))
      (node (ref "U2") (pin "15") (pinfunction "15_15") (pintype "unspecified"))
    )
    (net (code "95") (name "/TX(PB11)") (class "Default")
      (node (ref "U2") (pin "29") (pinfunction "29_29") (pintype "unspecified"))
      (node (ref "串口1") (pin "2") (pinfunction "2_2") (pintype "unspecified"))
    )
    (net (code "96") (name "/TX1(PA3)") (class "Default")
      (node (ref "STM32") (pin "9") (pinfunction "9_9") (pintype "unspecified"))
      (node (ref "串口屏") (pin "2") (pinfunction "2_2") (pintype "unspecified"))
    )
    (net (code "97") (name "/UP_9959(PF8)") (class "Default")
      (node (ref "AD9959") (pin "8") (pinfunction "8_8") (pintype "unspecified"))
      (node (ref "STM32") (pin "19") (pinfunction "19_19") (pintype "unspecified"))
    )
    (net (code "98") (name "/VBAT") (class "Default")
      (node (ref "U2") (pin "5") (pinfunction "5_5") (pintype "unspecified"))
    )
    (net (code "99") (name "Net-(LED1-+)") (class "Default")
      (node (ref "LED1") (pin "1") (pinfunction "+_1") (pintype "unspecified"))
      (node (ref "R11") (pin "2") (pinfunction "2_2") (pintype "input"))
    )
  )
)
